# IF_SEL.net
KiCad netlist of a schematic drawn in Altium Designer
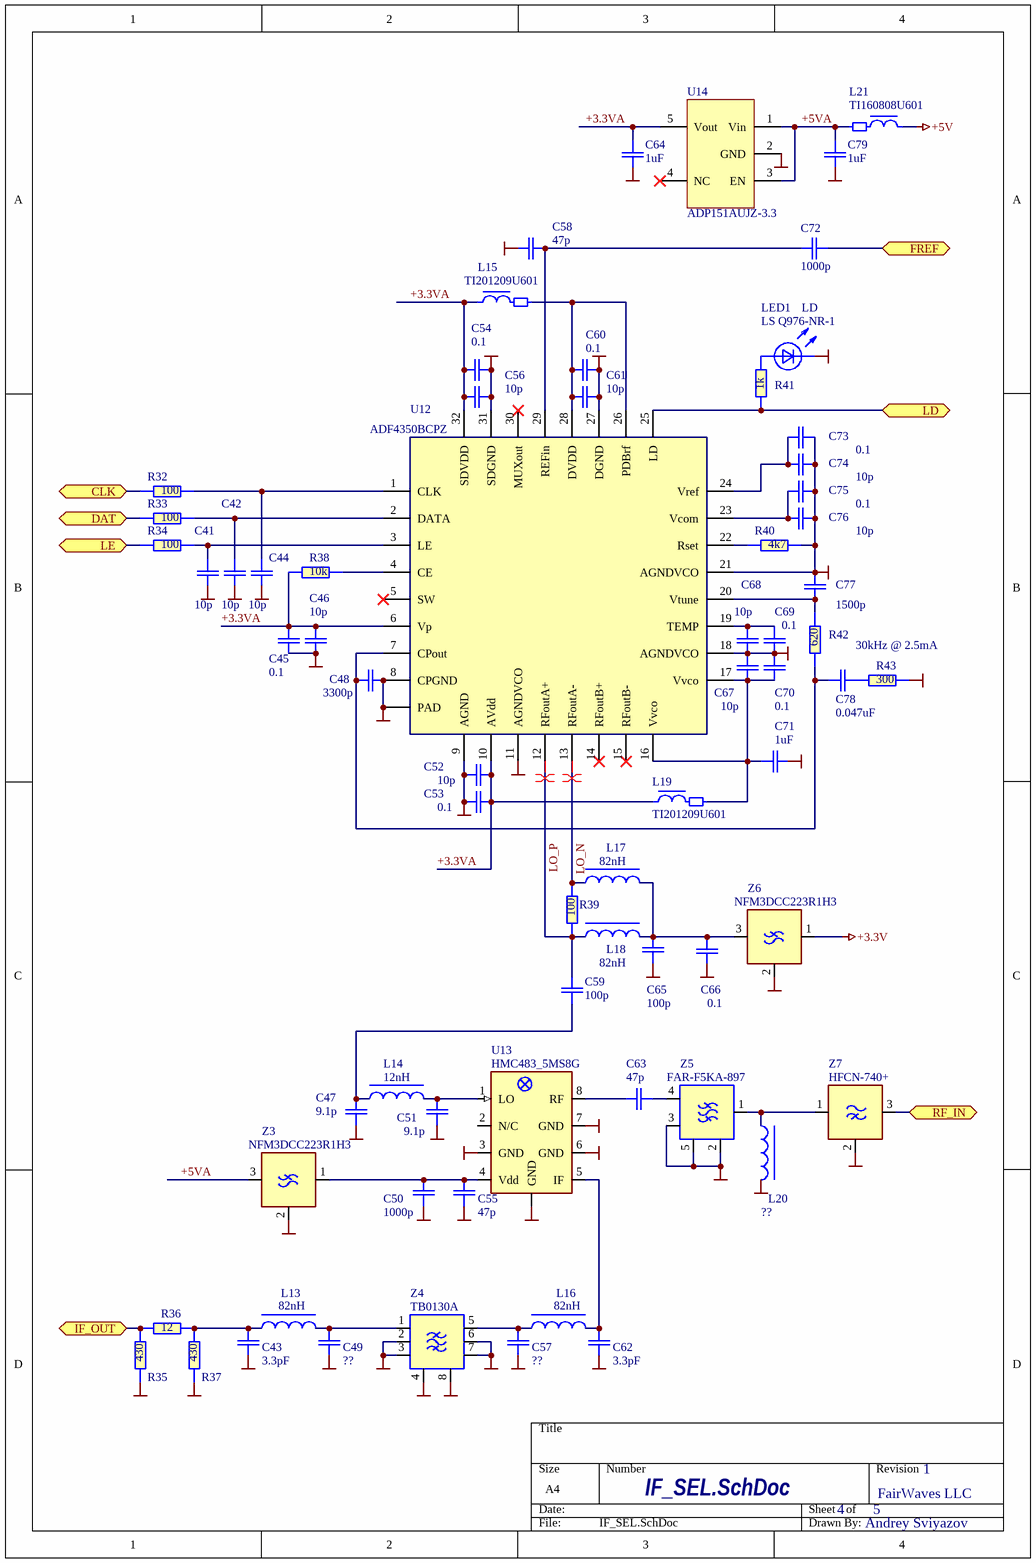
[diagram p0: IF_SEL.SchDoc]

(export (version "E")
  (design (tool "Eeschema 10.0.6"))
  (components
    (comp (ref "C41")
      (value "10p")
      (footprint "C0603-Phillips")
      (description "Capacitor")
      (fields (field (name "MANUFACTURER") "MURATA") (field (name "TOLERANCE") "20%"))
      (libsource (lib "Capacitors") (part "C0603"))
    )
    (comp (ref "C42")
      (value "10p")
      (footprint "C0603-Phillips")
      (description "Capacitor")
      (fields (field (name "MANUFACTURER") "MURATA") (field (name "TOLERANCE") "20%"))
      (libsource (lib "Capacitors") (part "C0603"))
    )
    (comp (ref "C43")
      (value "3.3pF")
      (footprint "C0603-Phillips")
      (description "Capacitor")
      (fields (field (name "MANUFACTURER") "MURATA") (field (name "TOLERANCE") "20%"))
      (libsource (lib "Capacitors") (part "C0603"))
    )
    (comp (ref "C44")
      (value "10p")
      (footprint "C0603-Phillips")
      (description "Capacitor")
      (fields (field (name "MANUFACTURER") "MURATA") (field (name "TOLERANCE") "20%"))
      (libsource (lib "Capacitors") (part "C0603"))
    )
    (comp (ref "C45")
      (value "0.1")
      (footprint "C0603-Phillips")
      (description "Capacitor")
      (fields (field (name "MANUFACTURER") "MURATA") (field (name "TOLERANCE") "20%"))
      (libsource (lib "Capacitors") (part "C0603"))
    )
    (comp (ref "C46")
      (value "10p")
      (footprint "C0603-Phillips")
      (description "Capacitor")
      (fields (field (name "MANUFACTURER") "MURATA") (field (name "TOLERANCE") "20%"))
      (libsource (lib "Capacitors") (part "C0603"))
    )
    (comp (ref "C47")
      (value "9.1p")
      (footprint "C0603-Phillips")
      (description "Capacitor")
      (fields (field (name "MANUFACTURER") "MURATA") (field (name "TOLERANCE") "20%"))
      (libsource (lib "Capacitors") (part "C0603"))
    )
    (comp (ref "C48")
      (value "3300p")
      (footprint "C0603-Phillips")
      (description "Capacitor")
      (fields (field (name "MANUFACTURER") "MURATA") (field (name "TOLERANCE") "20%"))
      (libsource (lib "Capacitors") (part "C0603"))
    )
    (comp (ref "C49")
      (value "??")
      (footprint "C0603-Phillips")
      (description "Capacitor")
      (fields (field (name "MANUFACTURER") "MURATA") (field (name "TOLERANCE") "20%"))
      (libsource (lib "Capacitors") (part "C0603"))
    )
    (comp (ref "C50")
      (value "1000p")
      (footprint "C0603-Phillips")
      (description "Capacitor")
      (fields (field (name "MANUFACTURER") "MURATA") (field (name "TOLERANCE") "20%"))
      (libsource (lib "Capacitors") (part "C0603"))
    )
    (comp (ref "C51")
      (value "9.1p")
      (footprint "C0603-Phillips")
      (description "Capacitor")
      (fields (field (name "MANUFACTURER") "MURATA") (field (name "TOLERANCE") "20%"))
      (libsource (lib "Capacitors") (part "C0603"))
    )
    (comp (ref "C52")
      (value "10p")
      (footprint "C0603-Phillips")
      (description "Capacitor")
      (fields (field (name "MANUFACTURER") "MURATA") (field (name "TOLERANCE") "20%"))
      (libsource (lib "Capacitors") (part "C0603"))
    )
    (comp (ref "C53")
      (value "0.1")
      (footprint "C0603-Phillips")
      (description "Capacitor")
      (fields (field (name "MANUFACTURER") "MURATA") (field (name "TOLERANCE") "20%"))
      (libsource (lib "Capacitors") (part "C0603"))
    )
    (comp (ref "C54")
      (value "0.1")
      (footprint "C0603-Phillips")
      (description "Capacitor")
      (fields (field (name "MANUFACTURER") "MURATA") (field (name "TOLERANCE") "20%"))
      (libsource (lib "Capacitors") (part "C0603"))
    )
    (comp (ref "C55")
      (value "47p")
      (footprint "C0603-Phillips")
      (description "Capacitor")
      (fields (field (name "MANUFACTURER") "MURATA") (field (name "TOLERANCE") "20%"))
      (libsource (lib "Capacitors") (part "C0603"))
    )
    (comp (ref "C56")
      (value "10p")
      (footprint "C0603-Phillips")
      (description "Capacitor")
      (fields (field (name "MANUFACTURER") "MURATA") (field (name "TOLERANCE") "20%"))
      (libsource (lib "Capacitors") (part "C0603"))
    )
    (comp (ref "C57")
      (value "??")
      (footprint "C0603-Phillips")
      (description "Capacitor")
      (fields (field (name "MANUFACTURER") "MURATA") (field (name "TOLERANCE") "20%"))
      (libsource (lib "Capacitors") (part "C0603"))
    )
    (comp (ref "C58")
      (value "47p")
      (footprint "C0603-Phillips")
      (description "Capacitor")
      (fields (field (name "MANUFACTURER") "MURATA") (field (name "TOLERANCE") "20%"))
      (libsource (lib "Capacitors") (part "C0603"))
    )
    (comp (ref "C59")
      (value "100p")
      (footprint "C0603-Phillips")
      (description "Capacitor")
      (fields (field (name "MANUFACTURER") "MURATA") (field (name "TOLERANCE") "20%"))
      (libsource (lib "Capacitors") (part "C0603"))
    )
    (comp (ref "C60")
      (value "0.1")
      (footprint "C0603-Phillips")
      (description "Capacitor")
      (fields (field (name "MANUFACTURER") "MURATA") (field (name "TOLERANCE") "20%"))
      (libsource (lib "Capacitors") (part "C0603"))
    )
    (comp (ref "C61")
      (value "10p")
      (footprint "C0603-Phillips")
      (description "Capacitor")
      (fields (field (name "MANUFACTURER") "MURATA") (field (name "TOLERANCE") "20%"))
      (libsource (lib "Capacitors") (part "C0603"))
    )
    (comp (ref "C62")
      (value "3.3pF")
      (footprint "C0603-Phillips")
      (description "Capacitor")
      (fields (field (name "MANUFACTURER") "MURATA") (field (name "TOLERANCE") "20%"))
      (libsource (lib "Capacitors") (part "C0603"))
    )
    (comp (ref "C63")
      (value "47p")
      (footprint "C0603-Phillips")
      (description "Capacitor")
      (fields (field (name "MANUFACTURER") "MURATA") (field (name "TOLERANCE") "20%"))
      (libsource (lib "Capacitors") (part "C0603"))
    )
    (comp (ref "C64")
      (value "1uF")
      (footprint "C0603-Phillips")
      (description "Capacitor")
      (fields (field (name "MANUFACTURER") "MURATA") (field (name "TOLERANCE") "20%"))
      (libsource (lib "Capacitors") (part "C0603"))
    )
    (comp (ref "C65")
      (value "100p")
      (footprint "C0603-Phillips")
      (description "Capacitor")
      (fields (field (name "MANUFACTURER") "MURATA") (field (name "TOLERANCE") "20%"))
      (libsource (lib "Capacitors") (part "C0603"))
    )
    (comp (ref "C66")
      (value "0.1")
      (footprint "C0603-Phillips")
      (description "Capacitor")
      (fields (field (name "MANUFACTURER") "MURATA") (field (name "TOLERANCE") "20%"))
      (libsource (lib "Capacitors") (part "C0603"))
    )
    (comp (ref "C67")
      (value "10p")
      (footprint "C0603-Phillips")
      (description "Capacitor")
      (fields (field (name "MANUFACTURER") "MURATA") (field (name "TOLERANCE") "20%"))
      (libsource (lib "Capacitors") (part "C0603"))
    )
    (comp (ref "C68")
      (value "10p")
      (footprint "C0603-Phillips")
      (description "Capacitor")
      (fields (field (name "MANUFACTURER") "MURATA") (field (name "TOLERANCE") "20%"))
      (libsource (lib "Capacitors") (part "C0603"))
    )
    (comp (ref "C69")
      (value "0.1")
      (footprint "C0603-Phillips")
      (description "Capacitor")
      (fields (field (name "MANUFACTURER") "MURATA") (field (name "TOLERANCE") "20%"))
      (libsource (lib "Capacitors") (part "C0603"))
    )
    (comp (ref "C70")
      (value "0.1")
      (footprint "C0603-Phillips")
      (description "Capacitor")
      (fields (field (name "MANUFACTURER") "MURATA") (field (name "TOLERANCE") "20%"))
      (libsource (lib "Capacitors") (part "C0603"))
    )
    (comp (ref "C71")
      (value "1uF")
      (footprint "C0603-Phillips")
      (description "Capacitor")
      (fields (field (name "MANUFACTURER") "MURATA") (field (name "TOLERANCE") "20%"))
      (libsource (lib "Capacitors") (part "C0603"))
    )
    (comp (ref "C72")
      (value "1000p")
      (footprint "C0603-Phillips")
      (description "Capacitor")
      (fields (field (name "MANUFACTURER") "MURATA") (field (name "TOLERANCE") "20%"))
      (libsource (lib "Capacitors") (part "C0603"))
    )
    (comp (ref "C73")
      (value "0.1")
      (footprint "C0603-Phillips")
      (description "Capacitor")
      (fields (field (name "MANUFACTURER") "MURATA") (field (name "TOLERANCE") "20%"))
      (libsource (lib "Capacitors") (part "C0603"))
    )
    (comp (ref "C74")
      (value "10p")
      (footprint "C0603-Phillips")
      (description "Capacitor")
      (fields (field (name "MANUFACTURER") "MURATA") (field (name "TOLERANCE") "20%"))
      (libsource (lib "Capacitors") (part "C0603"))
    )
    (comp (ref "C75")
      (value "0.1")
      (footprint "C0603-Phillips")
      (description "Capacitor")
      (fields (field (name "MANUFACTURER") "MURATA") (field (name "TOLERANCE") "20%"))
      (libsource (lib "Capacitors") (part "C0603"))
    )
    (comp (ref "C76")
      (value "10p")
      (footprint "C0603-Phillips")
      (description "Capacitor")
      (fields (field (name "MANUFACTURER") "MURATA") (field (name "TOLERANCE") "20%"))
      (libsource (lib "Capacitors") (part "C0603"))
    )
    (comp (ref "C77")
      (value "1500p")
      (footprint "C0603-Phillips")
      (description "Capacitor")
      (fields (field (name "MANUFACTURER") "MURATA") (field (name "TOLERANCE") "20%"))
      (libsource (lib "Capacitors") (part "C0603"))
    )
    (comp (ref "C78")
      (value "0.047uF")
      (footprint "C0603-Phillips")
      (description "Capacitor")
      (fields (field (name "MANUFACTURER") "MURATA") (field (name "TOLERANCE") "20%"))
      (libsource (lib "Capacitors") (part "C0603"))
    )
    (comp (ref "C79")
      (value "1uF")
      (footprint "C0603-Phillips")
      (description "Capacitor")
      (fields (field (name "MANUFACTURER") "MURATA") (field (name "TOLERANCE") "20%"))
      (libsource (lib "Capacitors") (part "C0603"))
    )
    (comp (ref "L13")
      (value "82nH")
      (footprint "TF160808-Phillips")
      (description "Coil")
      (fields (field (name "MANUFACTURER") "SMD"))
      (libsource (lib "Inductance Transformers") (part "TF160808"))
    )
    (comp (ref "L14")
      (value "12nH")
      (footprint "TF160808-Phillips")
      (description "Coil")
      (fields (field (name "MANUFACTURER") "SMD"))
      (libsource (lib "") (part "TF160808_1"))
    )
    (comp (ref "L15")
      (value "TI201209U601")
      (footprint "TI2012-Phillips")
      (description "Choke")
      (fields (field (name "MANUFACTURER") "MURATA"))
      (libsource (lib "Andy") (part "TI2012_1"))
    )
    (comp (ref "L16")
      (value "82nH")
      (footprint "TF160808-Phillips")
      (description "Coil")
      (fields (field (name "MANUFACTURER") "SMD"))
      (libsource (lib "Inductance Transformers") (part "TF160808"))
    )
    (comp (ref "L17")
      (value "82nH")
      (footprint "TF160808-Phillips")
      (description "Coil")
      (fields (field (name "MANUFACTURER") "SMD"))
      (libsource (lib "Inductance Transformers") (part "TF160808"))
    )
    (comp (ref "L18")
      (value "82nH")
      (footprint "TF160808-Phillips")
      (description "Coil")
      (fields (field (name "MANUFACTURER") "SMD"))
      (libsource (lib "Inductance Transformers") (part "TF160808"))
    )
    (comp (ref "L19")
      (value "TI201209U601")
      (footprint "TI2012-Phillips")
      (description "Choke")
      (fields (field (name "MANUFACTURER") "MURATA"))
      (libsource (lib "Andy") (part "TI2012_1"))
    )
    (comp (ref "L20")
      (value "??")
      (footprint "TF160808-Phillips")
      (description "Coil")
      (fields (field (name "MANUFACTURER") "SMD"))
      (libsource (lib "Inductance Transformers") (part "TF160808"))
    )
    (comp (ref "L21")
      (value "TI160808U601")
      (footprint "Andy:Ti160808-Phillips")
      (description "Choke")
      (fields (field (name "MANUFACTURER") "MURATA"))
      (libsource (lib "altium-import") (part "root_0_mirrored_TI160808_"))
    )
    (comp (ref "LED1")
      (value "LS Q976-NR-1")
      (footprint "LED-0603y")
      (description "LED SMD")
      (fields (field (name "MANUFACTURER") "OSRAM Opto Semi") (field (name "MISC") "LD"))
      (libsource (lib "altium-import") (part "root_1_mirrored_LED0603_"))
    )
    (comp (ref "R32")
      (value "100")
      (footprint "R0603-PHILLIPS")
      (description "Resistor")
      (fields (field (name "MANUFACTURER") "YAGEO") (field (name "TOLERANCE") "5%"))
      (libsource (lib "altium-import") (part "root_1_R0603_"))
    )
    (comp (ref "R33")
      (value "100")
      (footprint "R0603-PHILLIPS")
      (description "Resistor")
      (fields (field (name "MANUFACTURER") "YAGEO") (field (name "TOLERANCE") "5%"))
      (libsource (lib "altium-import") (part "root_1_R0603_"))
    )
    (comp (ref "R34")
      (value "100")
      (footprint "R0603-PHILLIPS")
      (description "Resistor")
      (fields (field (name "MANUFACTURER") "YAGEO") (field (name "TOLERANCE") "5%"))
      (libsource (lib "altium-import") (part "root_1_R0603_"))
    )
    (comp (ref "R35")
      (value "430")
      (footprint "R0603-PHILLIPS")
      (description "Resistor")
      (fields (field (name "MANUFACTURER") "YAGEO") (field (name "TOLERANCE") "5%"))
      (libsource (lib "altium-import") (part "root_2_R0603_"))
    )
    (comp (ref "R36")
      (value "12")
      (footprint "R0603-PHILLIPS")
      (description "Resistor")
      (fields (field (name "MANUFACTURER") "YAGEO") (field (name "TOLERANCE") "5%"))
      (libsource (lib "altium-import") (part "root_1_R0603_"))
    )
    (comp (ref "R37")
      (value "430")
      (footprint "R0603-PHILLIPS")
      (description "Resistor")
      (fields (field (name "MANUFACTURER") "YAGEO") (field (name "TOLERANCE") "5%"))
      (libsource (lib "altium-import") (part "root_2_R0603_"))
    )
    (comp (ref "R38")
      (value "10k")
      (footprint "R0603-PHILLIPS")
      (description "Resistor")
      (fields (field (name "MANUFACTURER") "YAGEO") (field (name "TOLERANCE") "5%"))
      (libsource (lib "altium-import") (part "root_1_R0603_"))
    )
    (comp (ref "R39")
      (value "100")
      (footprint "R0603-PHILLIPS")
      (description "Resistor")
      (fields (field (name "MANUFACTURER") "YAGEO") (field (name "TOLERANCE") "5%"))
      (libsource (lib "altium-import") (part "root_2_R0603_"))
    )
    (comp (ref "R40")
      (value "4k7")
      (footprint "R0603-PHILLIPS")
      (description "Resistor")
      (fields (field (name "MANUFACTURER") "YAGEO") (field (name "TOLERANCE") "5%"))
      (libsource (lib "altium-import") (part "root_1_R0603_"))
    )
    (comp (ref "R41")
      (value "1k")
      (footprint "R0603-PHILLIPS")
      (description "Resistor")
      (fields (field (name "MANUFACTURER") "YAGEO") (field (name "TOLERANCE") "5%"))
      (libsource (lib "altium-import") (part "root_2_R0603_"))
    )
    (comp (ref "R42")
      (value "620")
      (footprint "R0603-PHILLIPS")
      (description "Resistor")
      (fields (field (name "MANUFACTURER") "YAGEO") (field (name "TOLERANCE") "5%"))
      (libsource (lib "altium-import") (part "root_2_R0603_"))
    )
    (comp (ref "R43")
      (value "300")
      (footprint "R0603-PHILLIPS")
      (description "Resistor")
      (fields (field (name "MANUFACTURER") "YAGEO") (field (name "TOLERANCE") "5%"))
      (libsource (lib "altium-import") (part "root_1_R0603_"))
    )
    (comp (ref "U12")
      (value "ADF4350BCPZ")
      (footprint "CP-32-2")
      (description "IC")
      (fields (field (name "MANUFACTURER") "Analog Devices"))
      (libsource (lib "Andy") (part "ADF4350BCPZ"))
    )
    (comp (ref "U13")
      (value "HMC483_5MS8G")
      (footprint "MS8G")
      (description "IC")
      (fields (field (name "MANUFACTURER") "Hittite"))
      (libsource (lib "MicroCircuits") (part "HMC483_5MS8G"))
    )
    (comp (ref "U14")
      (value "ADP151AUJZ-3.3")
      (footprint "SOT-23-5[3.1x1.8/0.95]")
      (description "IC")
      (fields (field (name "MANUFACTURER") "AD"))
      (libsource (lib "Andy") (part "ADP151AUJZ"))
    )
    (comp (ref "Z3")
      (value "NFM3DCC223R1H3")
      (footprint "NFM3DC")
      (description "EMI_FILTER")
      (fields (field (name "MANUFACTURER") "Murata"))
      (libsource (lib "Andy") (part "NFM3DC"))
    )
    (comp (ref "Z4")
      (value "TB0130A")
      (footprint "DCC8_5x5")
      (description "SAW filter")
      (fields (field (name "MANUFACTURER") "Tai-SAW"))
      (libsource (lib "Andy") (part "SAW 5x5-8 SMD"))
    )
    (comp (ref "Z5")
      (value "FAR-F5KA-897")
      (footprint "SAW-1.4x1x0.5mm")
      (description "SAW Filter")
      (fields (field (name "MANUFACTURER") "Taiyo Yuden"))
      (libsource (lib "Andy") (part "SAW 1.4x1.0-5 SMD"))
    )
    (comp (ref "Z6")
      (value "NFM3DCC223R1H3")
      (footprint "NFM3DC")
      (description "EMI_FILTER")
      (fields (field (name "MANUFACTURER") "Murata"))
      (libsource (lib "Andy") (part "NFM3DC"))
    )
    (comp (ref "Z7")
      (value "HFCN-740+")
      (footprint "LFCN-HFCN")
      (description "High pass filter")
      (fields (field (name "MANUFACTURER") "MiniCircuits"))
      (libsource (lib "Andy") (part "HFCN-2700"))
    )
  )
  (nets
    (net (code "1") (name "+3.3V") (class "Default")
      (node (ref "Z6") (pin "1") (pinfunction "1_1") (pintype "passive"))
    )
    (net (code "2") (name "+5V") (class "Default")
      (node (ref "L21") (pin "1") (pinfunction "1_1") (pintype "passive"))
    )
    (net (code "3") (name "/+3.3VA") (class "Default")
      (node (ref "C45") (pin "2") (pinfunction "2_2") (pintype "passive"))
      (node (ref "C46") (pin "2") (pinfunction "2_2") (pintype "passive"))
      (node (ref "C52") (pin "1") (pinfunction "1_1") (pintype "passive"))
      (node (ref "C53") (pin "1") (pinfunction "1_1") (pintype "passive"))
      (node (ref "C54") (pin "1") (pinfunction "1_1") (pintype "passive"))
      (node (ref "C56") (pin "1") (pinfunction "1_1") (pintype "passive"))
      (node (ref "C64") (pin "2") (pinfunction "2_2") (pintype "passive"))
      (node (ref "L15") (pin "1") (pinfunction "1_1") (pintype "passive"))
      (node (ref "L19") (pin "1") (pinfunction "1_1") (pintype "passive"))
      (node (ref "R38") (pin "1") (pinfunction "1_1") (pintype "passive"))
      (node (ref "U12") (pin "10") (pinfunction "AVdd_10") (pintype "power_in"))
      (node (ref "U12") (pin "32") (pinfunction "SDVDD_32") (pintype "power_in"))
      (node (ref "U12") (pin "6") (pinfunction "Vp_6") (pintype "passive"))
      (node (ref "U14") (pin "5") (pinfunction "Vout_5") (pintype "passive"))
    )
    (net (code "4") (name "/+5VA") (class "Default")
      (node (ref "C79") (pin "2") (pinfunction "2_2") (pintype "passive"))
      (node (ref "L21") (pin "2") (pinfunction "2_2") (pintype "passive"))
      (node (ref "U14") (pin "1") (pinfunction "Vin_1") (pintype "passive"))
      (node (ref "U14") (pin "3") (pinfunction "EN_3") (pintype "passive"))
      (node (ref "Z3") (pin "3") (pinfunction "3_3") (pintype "passive"))
    )
    (net (code "5") (name "/CLK") (class "Default")
      (node (ref "R32") (pin "1") (pinfunction "1_1") (pintype "passive"))
    )
    (net (code "6") (name "/DAT") (class "Default")
      (node (ref "R33") (pin "1") (pinfunction "1_1") (pintype "passive"))
    )
    (net (code "7") (name "/FREF") (class "Default")
      (node (ref "C72") (pin "2") (pinfunction "2_2") (pintype "passive"))
    )
    (net (code "8") (name "/IF_OUT") (class "Default")
      (node (ref "R35") (pin "2") (pinfunction "2_2") (pintype "passive"))
      (node (ref "R36") (pin "1") (pinfunction "1_1") (pintype "passive"))
    )
    (net (code "9") (name "/LD") (class "Default")
      (node (ref "R41") (pin "1") (pinfunction "1_1") (pintype "passive"))
      (node (ref "U12") (pin "25") (pinfunction "LD_25") (pintype "passive"))
    )
    (net (code "10") (name "/LE") (class "Default")
      (node (ref "R34") (pin "1") (pinfunction "1_1") (pintype "passive"))
    )
    (net (code "11") (name "/LO_N") (class "Default")
      (node (ref "L17") (pin "1") (pinfunction "1_1") (pintype "passive"))
      (node (ref "R39") (pin "2") (pinfunction "2_2") (pintype "passive"))
      (node (ref "U12") (pin "13") (pinfunction "RFoutA-_13") (pintype "passive"))
    )
    (net (code "12") (name "/LO_P") (class "Default")
      (node (ref "C59") (pin "1") (pinfunction "1_1") (pintype "passive"))
      (node (ref "L18") (pin "1") (pinfunction "1_1") (pintype "passive"))
      (node (ref "R39") (pin "1") (pinfunction "1_1") (pintype "passive"))
      (node (ref "U12") (pin "12") (pinfunction "RFoutA+_12") (pintype "passive"))
    )
    (net (code "13") (name "/RF_IN") (class "Default")
      (node (ref "Z7") (pin "3") (pinfunction "3_3") (pintype "passive"))
    )
    (net (code "14") (name "GND") (class "Default")
      (node (ref "C41") (pin "1") (pinfunction "1_1") (pintype "passive"))
      (node (ref "C42") (pin "1") (pinfunction "1_1") (pintype "passive"))
      (node (ref "C43") (pin "1") (pinfunction "1_1") (pintype "passive"))
      (node (ref "C44") (pin "1") (pinfunction "1_1") (pintype "passive"))
      (node (ref "C45") (pin "1") (pinfunction "1_1") (pintype "passive"))
      (node (ref "C46") (pin "1") (pinfunction "1_1") (pintype "passive"))
      (node (ref "C47") (pin "2") (pinfunction "2_2") (pintype "passive"))
      (node (ref "C48") (pin "1") (pinfunction "1_1") (pintype "passive"))
      (node (ref "C49") (pin "1") (pinfunction "1_1") (pintype "passive"))
      (node (ref "C50") (pin "2") (pinfunction "2_2") (pintype "passive"))
      (node (ref "C51") (pin "2") (pinfunction "2_2") (pintype "passive"))
      (node (ref "C52") (pin "2") (pinfunction "2_2") (pintype "passive"))
      (node (ref "C53") (pin "2") (pinfunction "2_2") (pintype "passive"))
      (node (ref "C54") (pin "2") (pinfunction "2_2") (pintype "passive"))
      (node (ref "C55") (pin "2") (pinfunction "2_2") (pintype "passive"))
      (node (ref "C56") (pin "2") (pinfunction "2_2") (pintype "passive"))
      (node (ref "C57") (pin "1") (pinfunction "1_1") (pintype "passive"))
      (node (ref "C58") (pin "1") (pinfunction "1_1") (pintype "passive"))
      (node (ref "C60") (pin "2") (pinfunction "2_2") (pintype "passive"))
      (node (ref "C61") (pin "2") (pinfunction "2_2") (pintype "passive"))
      (node (ref "C62") (pin "1") (pinfunction "1_1") (pintype "passive"))
      (node (ref "C64") (pin "1") (pinfunction "1_1") (pintype "passive"))
      (node (ref "C65") (pin "2") (pinfunction "2_2") (pintype "passive"))
      (node (ref "C66") (pin "1") (pinfunction "1_1") (pintype "passive"))
      (node (ref "C67") (pin "2") (pinfunction "2_2") (pintype "passive"))
      (node (ref "C68") (pin "1") (pinfunction "1_1") (pintype "passive"))
      (node (ref "C69") (pin "1") (pinfunction "1_1") (pintype "passive"))
      (node (ref "C70") (pin "2") (pinfunction "2_2") (pintype "passive"))
      (node (ref "C71") (pin "1") (pinfunction "1_1") (pintype "passive"))
      (node (ref "C73") (pin "2") (pinfunction "2_2") (pintype "passive"))
      (node (ref "C74") (pin "2") (pinfunction "2_2") (pintype "passive"))
      (node (ref "C75") (pin "2") (pinfunction "2_2") (pintype "passive"))
      (node (ref "C76") (pin "2") (pinfunction "2_2") (pintype "passive"))
      (node (ref "C77") (pin "2") (pinfunction "2_2") (pintype "passive"))
      (node (ref "C79") (pin "1") (pinfunction "1_1") (pintype "passive"))
      (node (ref "L20") (pin "2") (pinfunction "2_2") (pintype "passive"))
      (node (ref "LED1") (pin "1") (pinfunction "K_1") (pintype "passive"))
      (node (ref "R35") (pin "1") (pinfunction "1_1") (pintype "passive"))
      (node (ref "R37") (pin "1") (pinfunction "1_1") (pintype "passive"))
      (node (ref "R40") (pin "2") (pinfunction "2_2") (pintype "passive"))
      (node (ref "R43") (pin "2") (pinfunction "2_2") (pintype "passive"))
      (node (ref "U12") (pin "0") (pinfunction "PAD_0") (pintype "passive"))
      (node (ref "U12") (pin "11") (pinfunction "AGNDVCO_11") (pintype "power_in"))
      (node (ref "U12") (pin "18") (pinfunction "AGNDVCO_18") (pintype "power_in"))
      (node (ref "U12") (pin "21") (pinfunction "AGNDVCO_21") (pintype "power_in"))
      (node (ref "U12") (pin "27") (pinfunction "DGND_27") (pintype "power_in"))
      (node (ref "U12") (pin "31") (pinfunction "SDGND_31") (pintype "power_in"))
      (node (ref "U12") (pin "8") (pinfunction "CPGND_8") (pintype "passive"))
      (node (ref "U12") (pin "9") (pinfunction "AGND_9") (pintype "power_in"))
      (node (ref "U13") (pin "0") (pinfunction "GND_0") (pintype "power_in"))
      (node (ref "U13") (pin "3") (pinfunction "GND_3") (pintype "power_in"))
      (node (ref "U13") (pin "6") (pinfunction "GND_6") (pintype "power_in"))
      (node (ref "U13") (pin "7") (pinfunction "GND_7") (pintype "power_in"))
      (node (ref "U14") (pin "2") (pinfunction "GND_2") (pintype "passive"))
      (node (ref "Z3") (pin "2") (pinfunction "2_2") (pintype "passive"))
      (node (ref "Z4") (pin "2") (pinfunction "In2_2") (pintype "power_in"))
      (node (ref "Z4") (pin "3") (pinfunction "In3_3") (pintype "power_in"))
      (node (ref "Z4") (pin "4") (pinfunction "Gnd_4") (pintype "power_in"))
      (node (ref "Z4") (pin "6") (pinfunction "Out2_6") (pintype "power_in"))
      (node (ref "Z4") (pin "7") (pinfunction "Out3_7") (pintype "power_in"))
      (node (ref "Z4") (pin "8") (pinfunction "Gnd_8") (pintype "power_in"))
      (node (ref "Z5") (pin "2") (pinfunction "GND_2") (pintype "power_in"))
      (node (ref "Z5") (pin "3") (pinfunction "~{Out}_3") (pintype "passive"))
      (node (ref "Z5") (pin "5") (pinfunction "GND_5") (pintype "power_in"))
      (node (ref "Z6") (pin "2") (pinfunction "2_2") (pintype "passive"))
      (node (ref "Z7") (pin "2") (pinfunction "2_2") (pintype "passive"))
    )
    (net (code "15") (name "Net-(C43-Pad2)") (class "Default")
      (node (ref "C43") (pin "2") (pinfunction "2_2") (pintype "passive"))
      (node (ref "L13") (pin "1") (pinfunction "1_1") (pintype "passive"))
      (node (ref "R36") (pin "2") (pinfunction "2_2") (pintype "passive"))
      (node (ref "R37") (pin "2") (pinfunction "2_2") (pintype "passive"))
    )
    (net (code "16") (name "Net-(C47-Pad1)") (class "Default")
      (node (ref "C47") (pin "1") (pinfunction "1_1") (pintype "passive"))
      (node (ref "C59") (pin "2") (pinfunction "2_2") (pintype "passive"))
      (node (ref "L14") (pin "2") (pinfunction "2_2") (pintype "passive"))
    )
    (net (code "17") (name "Net-(C65-Pad1)") (class "Default")
      (node (ref "C65") (pin "1") (pinfunction "1_1") (pintype "passive"))
      (node (ref "C66") (pin "2") (pinfunction "2_2") (pintype "passive"))
      (node (ref "L17") (pin "2") (pinfunction "2_2") (pintype "passive"))
      (node (ref "L18") (pin "2") (pinfunction "2_2") (pintype "passive"))
      (node (ref "Z6") (pin "3") (pinfunction "3_3") (pintype "passive"))
    )
    (net (code "18") (name "Net-(C67-Pad1)") (class "Default")
      (node (ref "C67") (pin "1") (pinfunction "1_1") (pintype "passive"))
      (node (ref "C70") (pin "1") (pinfunction "1_1") (pintype "passive"))
      (node (ref "C71") (pin "2") (pinfunction "2_2") (pintype "passive"))
      (node (ref "L19") (pin "2") (pinfunction "2_2") (pintype "passive"))
      (node (ref "U12") (pin "16") (pinfunction "Vvco_16") (pintype "passive"))
      (node (ref "U12") (pin "17") (pinfunction "Vvco_17") (pintype "passive"))
    )
    (net (code "19") (name "Net-(C78-Pad1)") (class "Default")
      (node (ref "C78") (pin "1") (pinfunction "1_1") (pintype "passive"))
      (node (ref "R43") (pin "1") (pinfunction "1_1") (pintype "passive"))
    )
    (net (code "20") (name "Net-(LED1-A)") (class "Default")
      (node (ref "LED1") (pin "2") (pinfunction "A_2") (pintype "passive"))
      (node (ref "R41") (pin "2") (pinfunction "2_2") (pintype "passive"))
    )
    (net (code "21") (name "Net-(U12-CE)") (class "Default")
      (node (ref "R38") (pin "2") (pinfunction "2_2") (pintype "passive"))
      (node (ref "U12") (pin "4") (pinfunction "CE_4") (pintype "passive"))
    )
    (net (code "22") (name "Net-(U12-CLK)") (class "Default")
      (node (ref "C44") (pin "2") (pinfunction "2_2") (pintype "passive"))
      (node (ref "R32") (pin "2") (pinfunction "2_2") (pintype "passive"))
      (node (ref "U12") (pin "1") (pinfunction "CLK_1") (pintype "passive"))
    )
    (net (code "23") (name "Net-(U12-CPout)") (class "Default")
      (node (ref "C48") (pin "2") (pinfunction "2_2") (pintype "passive"))
      (node (ref "C78") (pin "2") (pinfunction "2_2") (pintype "passive"))
      (node (ref "R42") (pin "1") (pinfunction "1_1") (pintype "passive"))
      (node (ref "U12") (pin "7") (pinfunction "CPout_7") (pintype "passive"))
    )
    (net (code "24") (name "Net-(U12-DATA)") (class "Default")
      (node (ref "C42") (pin "2") (pinfunction "2_2") (pintype "passive"))
      (node (ref "R33") (pin "2") (pinfunction "2_2") (pintype "passive"))
      (node (ref "U12") (pin "2") (pinfunction "DATA_2") (pintype "passive"))
    )
    (net (code "25") (name "Net-(U12-DVDD)") (class "Default")
      (node (ref "C60") (pin "1") (pinfunction "1_1") (pintype "passive"))
      (node (ref "C61") (pin "1") (pinfunction "1_1") (pintype "passive"))
      (node (ref "L15") (pin "2") (pinfunction "2_2") (pintype "passive"))
      (node (ref "U12") (pin "26") (pinfunction "PDBrf_26") (pintype "passive"))
      (node (ref "U12") (pin "28") (pinfunction "DVDD_28") (pintype "power_in"))
    )
    (net (code "26") (name "Net-(U12-LE)") (class "Default")
      (node (ref "C41") (pin "2") (pinfunction "2_2") (pintype "passive"))
      (node (ref "R34") (pin "2") (pinfunction "2_2") (pintype "passive"))
      (node (ref "U12") (pin "3") (pinfunction "LE_3") (pintype "passive"))
    )
    (net (code "27") (name "Net-(U12-REFin)") (class "Default")
      (node (ref "C58") (pin "2") (pinfunction "2_2") (pintype "passive"))
      (node (ref "C72") (pin "1") (pinfunction "1_1") (pintype "passive"))
      (node (ref "U12") (pin "29") (pinfunction "REFin_29") (pintype "passive"))
    )
    (net (code "28") (name "Net-(U12-Rset)") (class "Default")
      (node (ref "R40") (pin "1") (pinfunction "1_1") (pintype "passive"))
      (node (ref "U12") (pin "22") (pinfunction "Rset_22") (pintype "passive"))
    )
    (net (code "29") (name "Net-(U12-TEMP)") (class "Default")
      (node (ref "C68") (pin "2") (pinfunction "2_2") (pintype "passive"))
      (node (ref "C69") (pin "2") (pinfunction "2_2") (pintype "passive"))
      (node (ref "U12") (pin "19") (pinfunction "TEMP_19") (pintype "passive"))
    )
    (net (code "30") (name "Net-(U12-Vcom)") (class "Default")
      (node (ref "C75") (pin "1") (pinfunction "1_1") (pintype "passive"))
      (node (ref "C76") (pin "1") (pinfunction "1_1") (pintype "passive"))
      (node (ref "U12") (pin "23") (pinfunction "Vcom_23") (pintype "passive"))
    )
    (net (code "31") (name "Net-(U12-Vref)") (class "Default")
      (node (ref "C73") (pin "1") (pinfunction "1_1") (pintype "passive"))
      (node (ref "C74") (pin "1") (pinfunction "1_1") (pintype "passive"))
      (node (ref "U12") (pin "24") (pinfunction "Vref_24") (pintype "passive"))
    )
    (net (code "32") (name "Net-(U12-Vtune)") (class "Default")
      (node (ref "C77") (pin "1") (pinfunction "1_1") (pintype "passive"))
      (node (ref "R42") (pin "2") (pinfunction "2_2") (pintype "passive"))
      (node (ref "U12") (pin "20") (pinfunction "Vtune_20") (pintype "passive"))
    )
    (net (code "33") (name "Net-(U13-IF)") (class "Default")
      (node (ref "C62") (pin "2") (pinfunction "2_2") (pintype "passive"))
      (node (ref "L16") (pin "2") (pinfunction "2_2") (pintype "passive"))
      (node (ref "U13") (pin "5") (pinfunction "IF_5") (pintype "bidirectional"))
    )
    (net (code "34") (name "Net-(U13-LO)") (class "Default")
      (node (ref "C51") (pin "1") (pinfunction "1_1") (pintype "passive"))
      (node (ref "L14") (pin "1") (pinfunction "1_1") (pintype "passive"))
      (node (ref "U13") (pin "1") (pinfunction "LO_1") (pintype "input"))
    )
    (net (code "35") (name "Net-(U13-RF)") (class "Default")
      (node (ref "C63") (pin "1") (pinfunction "1_1") (pintype "passive"))
      (node (ref "U13") (pin "8") (pinfunction "RF_8") (pintype "bidirectional"))
    )
    (net (code "36") (name "Net-(U13-Vdd)") (class "Default")
      (node (ref "C50") (pin "1") (pinfunction "1_1") (pintype "passive"))
      (node (ref "C55") (pin "1") (pinfunction "1_1") (pintype "passive"))
      (node (ref "U13") (pin "4") (pinfunction "Vdd_4") (pintype "power_in"))
      (node (ref "Z3") (pin "1") (pinfunction "1_1") (pintype "passive"))
    )
    (net (code "37") (name "Net-(Z4-IN1)") (class "Default")
      (node (ref "C49") (pin "2") (pinfunction "2_2") (pintype "passive"))
      (node (ref "L13") (pin "2") (pinfunction "2_2") (pintype "passive"))
      (node (ref "Z4") (pin "1") (pinfunction "IN1_1") (pintype "passive"))
    )
    (net (code "38") (name "Net-(Z4-Out1)") (class "Default")
      (node (ref "C57") (pin "2") (pinfunction "2_2") (pintype "passive"))
      (node (ref "L16") (pin "1") (pinfunction "1_1") (pintype "passive"))
      (node (ref "Z4") (pin "5") (pinfunction "Out1_5") (pintype "passive"))
    )
    (net (code "39") (name "Net-(Z5-IN)") (class "Default")
      (node (ref "L20") (pin "1") (pinfunction "1_1") (pintype "passive"))
      (node (ref "Z5") (pin "1") (pinfunction "IN_1") (pintype "passive"))
      (node (ref "Z7") (pin "1") (pinfunction "1_1") (pintype "passive"))
    )
    (net (code "40") (name "Net-(Z5-Out)") (class "Default")
      (node (ref "C63") (pin "2") (pinfunction "2_2") (pintype "passive"))
      (node (ref "Z5") (pin "4") (pinfunction "Out_4") (pintype "passive"))
    )
    (net (code "41") (name "unconnected-(U12-MUXout-Pad30)") (class "Default")
      (node (ref "U12") (pin "30") (pinfunction "MUXout_30") (pintype "passive+no_connect"))
    )
    (net (code "42") (name "unconnected-(U12-RFoutB+-Pad14)") (class "Default")
      (node (ref "U12") (pin "14") (pinfunction "RFoutB+_14") (pintype "passive+no_connect"))
    )
    (net (code "43") (name "unconnected-(U12-RFoutB--Pad15)") (class "Default")
      (node (ref "U12") (pin "15") (pinfunction "RFoutB-_15") (pintype "passive+no_connect"))
    )
    (net (code "44") (name "unconnected-(U12-SW-Pad5)") (class "Default")
      (node (ref "U12") (pin "5") (pinfunction "SW_5") (pintype "passive+no_connect"))
    )
    (net (code "45") (name "unconnected-(U13-N{slash}C-Pad2)") (class "Default")
      (node (ref "U13") (pin "2") (pinfunction "N/C_2") (pintype "passive"))
    )
    (net (code "46") (name "unconnected-(U14-NC-Pad4)") (class "Default")
      (node (ref "U14") (pin "4") (pinfunction "NC_4") (pintype "passive+no_connect"))
    )
  )
)
